# PIR_datalogger.net
KiCad netlist of a schematic drawn in EAGLE
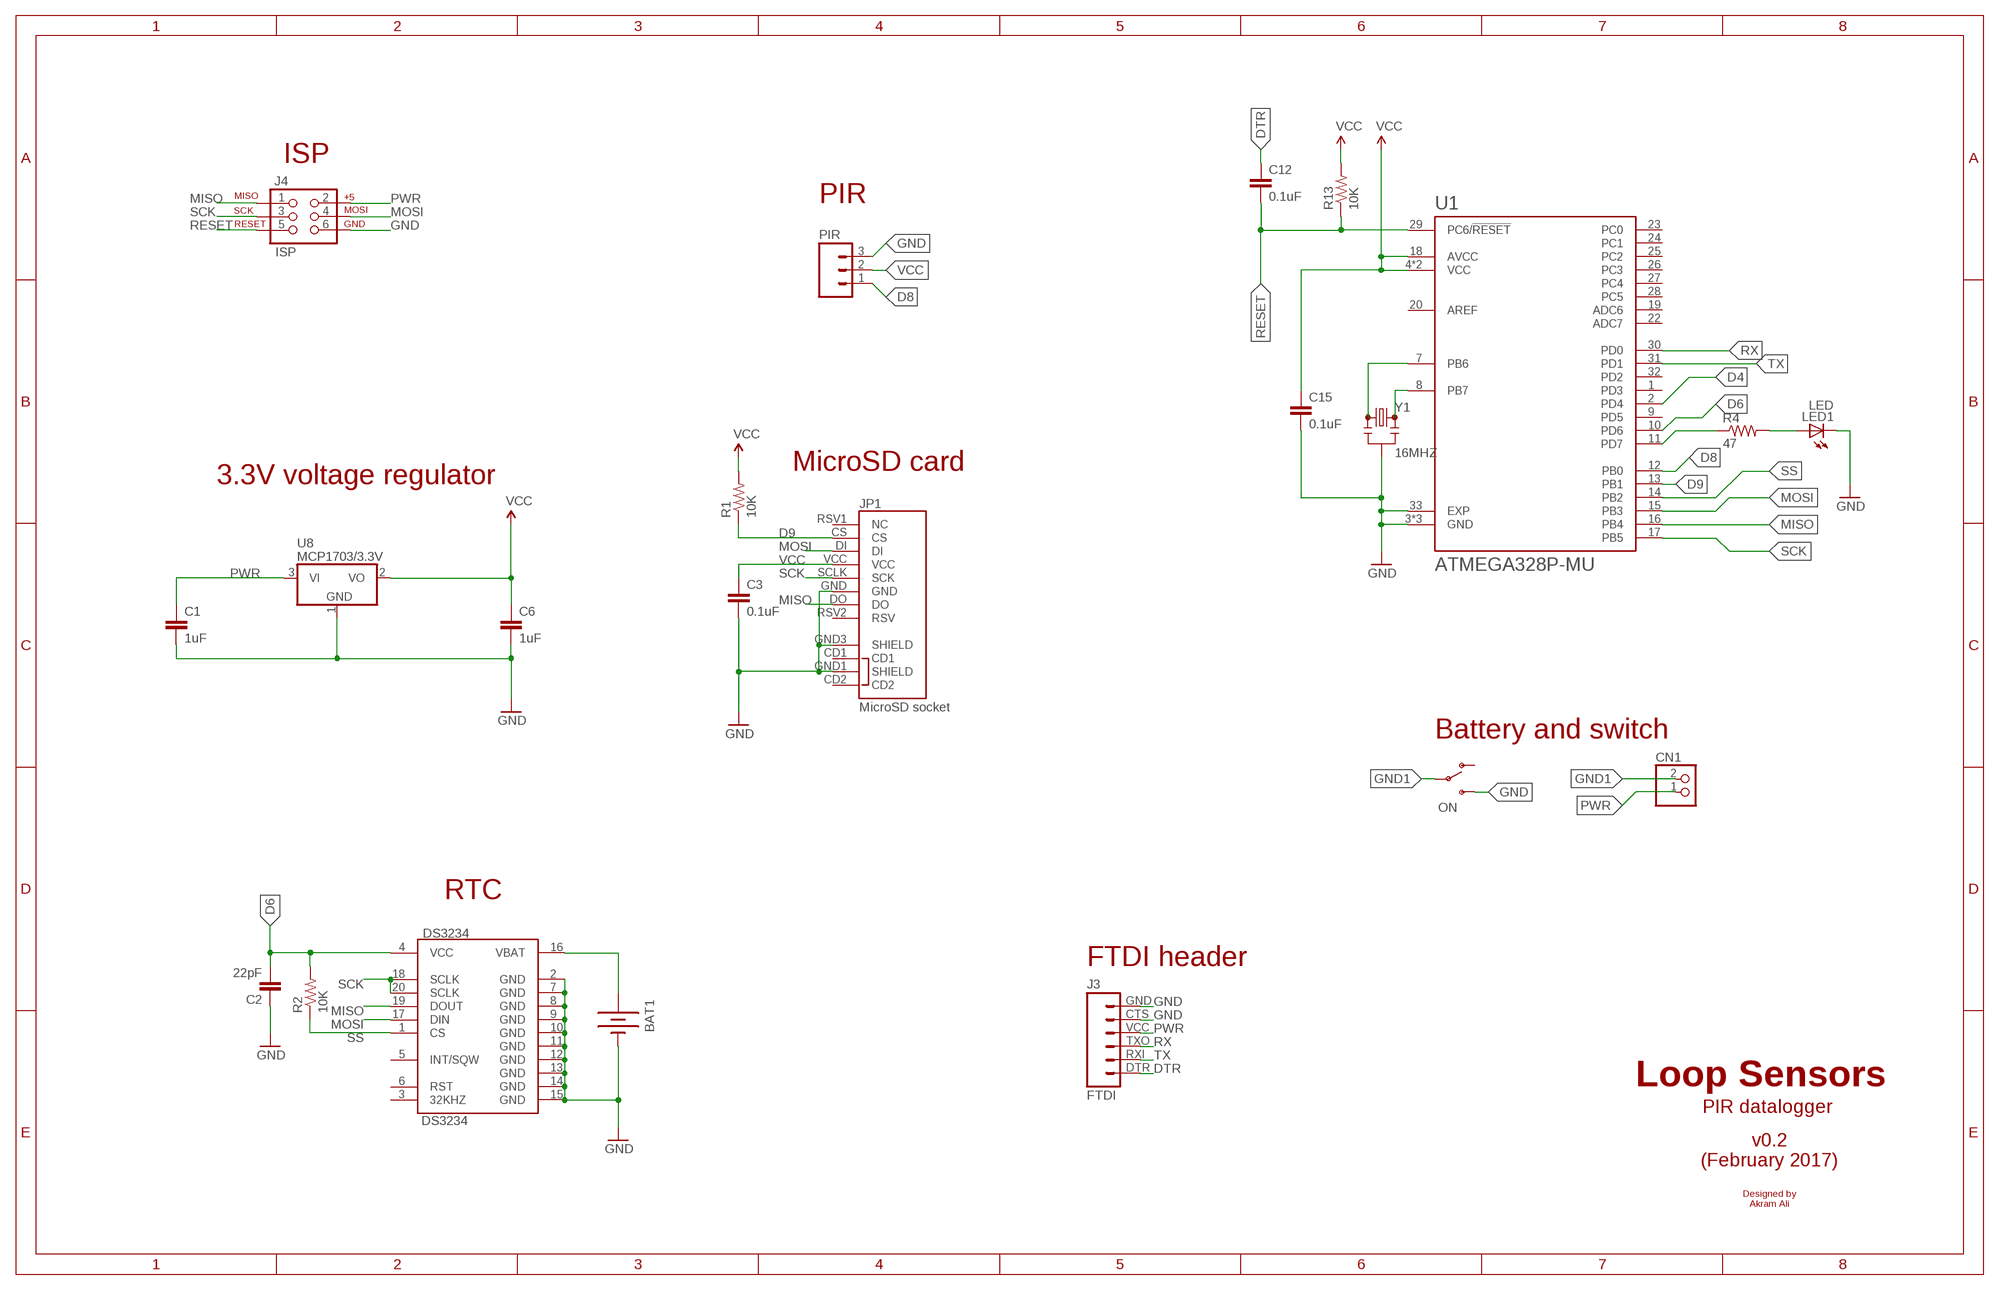
[diagram p0: schematic, sheet 1]

(export (version "E")
  (design (tool "Eeschema 10.0.6"))
  (components
    (comp (ref "BAT1")
      (value "BATTERY12MM")
      (footprint "eagle-import:BATTCON_12MM")
      (fields (field (name "MPN") "3000"))
      (libsource (lib "eagle-import") (part "BATTERY12MM"))
    )
    (comp (ref "C1")
      (value "1uF")
      (footprint "eagle-import:0805")
      (fields (field (name "MPN") "CC0805KKX7R7BB105"))
      (libsource (lib "eagle-import") (part "CAP0805"))
    )
    (comp (ref "C2")
      (value "22pF")
      (footprint "eagle-import:0805")
      (fields (field (name "MPN") "AC0805KRX7R9BB104"))
      (libsource (lib "eagle-import") (part "SparkFun-Passives_CAP0805"))
    )
    (comp (ref "C3")
      (value "0.1uF")
      (footprint "eagle-import:0805")
      (fields (field (name "MPN") "AC0805KRX7R9BB104"))
      (libsource (lib "eagle-import") (part "SparkFun-Passives_CAP0805"))
    )
    (comp (ref "C6")
      (value "1uF")
      (footprint "eagle-import:0805")
      (fields (field (name "MPN") "CC0805KKX7R7BB105"))
      (libsource (lib "eagle-import") (part "CAP0805"))
    )
    (comp (ref "C12")
      (value "0.1uF")
      (footprint "eagle-import:0805")
      (fields (field (name "MPN") "AC0805KRX7R9BB104"))
      (libsource (lib "eagle-import") (part "SparkFun-Passives_CAP0805"))
    )
    (comp (ref "C15")
      (value "0.1uF")
      (footprint "eagle-import:0805")
      (fields (field (name "MPN") "AC0805KRX7R9BB104"))
      (libsource (lib "eagle-import") (part "SparkFun-Passives_CAP0805"))
    )
    (comp (ref "CN1")
      (value "JST_2PIN-SMT-RA")
      (footprint "eagle-import:JST-PH-2-SMT-RA")
      (libsource (lib "eagle-import") (part "JST_2PIN-SMT-RA"))
    )
    (comp (ref "DS3234")
      (value "DS3234")
      (footprint "eagle-import:DS3234")
      (fields (field (name "MPN") "DS3234S#"))
      (libsource (lib "eagle-import") (part "DS3234"))
    )
    (comp (ref "J3")
      (value "FTDI")
      (footprint "eagle-import:FTDI_BASIC")
      (libsource (lib "eagle-import") (part "FTDI_BASICPTH"))
    )
    (comp (ref "J4")
      (value "ISP")
      (footprint "eagle-import:2X3")
      (libsource (lib "eagle-import") (part "AVR_SPI_PRG_6PTH"))
    )
    (comp (ref "JP1")
      (value "MicroSD socket")
      (footprint "eagle-import:MICRO-SD-SOCKET-PP")
      (libsource (lib "eagle-import") (part "USD-SOCKETNEW"))
    )
    (comp (ref "LED1")
      (value "LED")
      (footprint "eagle-import:CHIPLED_0805")
      (fields (field (name "MPN") "150080BS75000"))
      (libsource (lib "eagle-import") (part "LEDCHIPLED_0805"))
    )
    (comp (ref "ON")
      (value "SWITCH-SPDT-SMD-A")
      (footprint "eagle-import:SWITCH-SPST-SMD-A")
      (libsource (lib "eagle-import") (part "SWITCH-SPDT-SMD-A"))
    )
    (comp (ref "PIR")
      (value "M03PTH")
      (footprint "eagle-import:1X03")
      (libsource (lib "eagle-import") (part "M03PTH"))
    )
    (comp (ref "R1")
      (value "10K")
      (footprint "eagle-import:0805")
      (fields (field (name "MPN") "RC0805JR-0710KL"))
      (libsource (lib "eagle-import") (part "RESISTOR0805-RES"))
    )
    (comp (ref "R2")
      (value "10K")
      (footprint "eagle-import:0805")
      (fields (field (name "MPN") "RC0805JR-0710KL"))
      (libsource (lib "eagle-import") (part "RESISTOR0805-RES"))
    )
    (comp (ref "R4")
      (value "47")
      (footprint "eagle-import:0805")
      (fields (field (name "MPN") "RC0805JR-0747RL"))
      (libsource (lib "eagle-import") (part "SparkFun-Resistors_RESISTOR0805-RES"))
    )
    (comp (ref "R13")
      (value "10K")
      (footprint "eagle-import:0805")
      (fields (field (name "MPN") "RC0805JR-0710KL"))
      (libsource (lib "eagle-import") (part "RESISTOR0805-RES"))
    )
    (comp (ref "U1")
      (value "ATMEGA328P-MU")
      (footprint "eagle-import:QFN50P500X500X100-33N")
      (fields (field (name "MF") "Atmel"))
      (libsource (lib "eagle-import") (part "ATMEGA328P-MU"))
    )
    (comp (ref "U8")
      (value "MCP1703/3.3V")
      (footprint "eagle-import:SOT23")
      (fields (field (name "MPN") "MCP1703T-2502E/CB"))
      (libsource (lib "eagle-import") (part "MCP1703CB"))
    )
    (comp (ref "Y1")
      (value "16MHZ")
      (footprint "eagle-import:RESONATOR-SMD")
      (fields (field (name "MPN") "CSTCE16M0V53-R0"))
      (libsource (lib "eagle-import") (part "RESONATOR16MHZ"))
    )
  )
  (nets
    (net (code "1") (name "D4") (class "Default")
      (node (ref "U1") (pin "2") (pinfunction "PD4_2") (pintype "bidirectional"))
    )
    (net (code "2") (name "D6") (class "Default")
      (node (ref "C2") (pin "2") (pinfunction "2_2") (pintype "passive"))
      (node (ref "DS3234") (pin "4") (pinfunction "VCC_4") (pintype "bidirectional"))
      (node (ref "R2") (pin "2") (pinfunction "2_2") (pintype "passive"))
      (node (ref "U1") (pin "10") (pinfunction "PD6_10") (pintype "bidirectional"))
    )
    (net (code "3") (name "D8") (class "Default")
      (node (ref "PIR") (pin "1") (pinfunction "1_1") (pintype "passive"))
      (node (ref "U1") (pin "12") (pinfunction "PB0_12") (pintype "bidirectional"))
    )
    (net (code "4") (name "D9") (class "Default")
      (node (ref "JP1") (pin "CS") (pinfunction "CS_CS") (pintype "bidirectional"))
      (node (ref "R1") (pin "1") (pinfunction "1_1") (pintype "passive"))
      (node (ref "U1") (pin "13") (pinfunction "PB1_13") (pintype "bidirectional"))
    )
    (net (code "5") (name "DTR") (class "Default")
      (node (ref "C12") (pin "1") (pinfunction "1_1") (pintype "passive"))
      (node (ref "J3") (pin "DTR") (pinfunction "1_DTR") (pintype "passive"))
    )
    (net (code "6") (name "GND") (class "Default")
      (node (ref "BAT1") (pin "GND") (pinfunction "-_GND") (pintype "power_in"))
      (node (ref "C1") (pin "2") (pinfunction "2_2") (pintype "passive"))
      (node (ref "C15") (pin "2") (pinfunction "2_2") (pintype "passive"))
      (node (ref "C2") (pin "1") (pinfunction "1_1") (pintype "passive"))
      (node (ref "C3") (pin "2") (pinfunction "2_2") (pintype "passive"))
      (node (ref "C6") (pin "2") (pinfunction "2_2") (pintype "passive"))
      (node (ref "DS3234") (pin "10") (pinfunction "GND_10") (pintype "bidirectional"))
      (node (ref "DS3234") (pin "11") (pinfunction "GND_11") (pintype "bidirectional"))
      (node (ref "DS3234") (pin "12") (pinfunction "GND_12") (pintype "bidirectional"))
      (node (ref "DS3234") (pin "13") (pinfunction "GND_13") (pintype "bidirectional"))
      (node (ref "DS3234") (pin "14") (pinfunction "GND_14") (pintype "bidirectional"))
      (node (ref "DS3234") (pin "15") (pinfunction "GND_15") (pintype "bidirectional"))
      (node (ref "DS3234") (pin "2") (pinfunction "GND_2") (pintype "bidirectional"))
      (node (ref "DS3234") (pin "7") (pinfunction "GND_7") (pintype "bidirectional"))
      (node (ref "DS3234") (pin "8") (pinfunction "GND_8") (pintype "bidirectional"))
      (node (ref "DS3234") (pin "9") (pinfunction "GND_9") (pintype "bidirectional"))
      (node (ref "J3") (pin "CTS") (pinfunction "5_CTS") (pintype "passive"))
      (node (ref "J3") (pin "GND") (pinfunction "6_GND") (pintype "passive"))
      (node (ref "J4") (pin "6") (pinfunction "6_6") (pintype "passive"))
      (node (ref "JP1") (pin "GND") (pinfunction "GND_GND") (pintype "bidirectional"))
      (node (ref "JP1") (pin "GND1") (pinfunction "SHIELD_GND1") (pintype "bidirectional"))
      (node (ref "JP1") (pin "GND3") (pinfunction "SHIELD_GND3") (pintype "bidirectional"))
      (node (ref "LED1") (pin "C") (pinfunction "C_C") (pintype "passive"))
      (node (ref "ON") (pin "3") (pinfunction "S_3") (pintype "passive"))
      (node (ref "PIR") (pin "3") (pinfunction "3_3") (pintype "passive"))
      (node (ref "U1") (pin "21") (pinfunction "GND_21") (pintype "power_in"))
      (node (ref "U1") (pin "3") (pinfunction "GND_3") (pintype "power_in"))
      (node (ref "U1") (pin "33") (pinfunction "EXP_33") (pintype "power_in"))
      (node (ref "U1") (pin "5") (pinfunction "GND_5") (pintype "power_in"))
      (node (ref "U8") (pin "1") (pinfunction "GND_1") (pintype "passive"))
      (node (ref "Y1") (pin "2") (pinfunction "2_2") (pintype "passive"))
    )
    (net (code "7") (name "GND1") (class "Default")
      (node (ref "CN1") (pin "2") (pinfunction "1_2") (pintype "passive"))
      (node (ref "ON") (pin "2") (pinfunction "P_2") (pintype "passive"))
    )
    (net (code "8") (name "MISO") (class "Default")
      (node (ref "DS3234") (pin "19") (pinfunction "DOUT_19") (pintype "bidirectional"))
      (node (ref "J4") (pin "1") (pinfunction "1_1") (pintype "passive"))
      (node (ref "JP1") (pin "DO") (pinfunction "DO_DO") (pintype "bidirectional"))
      (node (ref "U1") (pin "16") (pinfunction "PB4_16") (pintype "bidirectional"))
    )
    (net (code "9") (name "MOSI") (class "Default")
      (node (ref "DS3234") (pin "17") (pinfunction "DIN_17") (pintype "bidirectional"))
      (node (ref "J4") (pin "4") (pinfunction "4_4") (pintype "passive"))
      (node (ref "JP1") (pin "DI") (pinfunction "DI_DI") (pintype "bidirectional"))
      (node (ref "U1") (pin "15") (pinfunction "PB3_15") (pintype "bidirectional"))
    )
    (net (code "10") (name "Net-(BAT1-+)") (class "Default")
      (node (ref "BAT1") (pin "PWR@1") (pinfunction "+_PWR@1") (pintype "power_in"))
      (node (ref "DS3234") (pin "16") (pinfunction "VBAT_16") (pintype "bidirectional"))
    )
    (net (code "11") (name "Net-(LED1-PadA)") (class "Default")
      (node (ref "LED1") (pin "A") (pinfunction "A_A") (pintype "passive"))
      (node (ref "R4") (pin "2") (pinfunction "2_2") (pintype "passive"))
    )
    (net (code "12") (name "Net-(U1-PB6)") (class "Default")
      (node (ref "U1") (pin "7") (pinfunction "PB6_7") (pintype "bidirectional"))
      (node (ref "Y1") (pin "1") (pinfunction "1_1") (pintype "passive"))
    )
    (net (code "13") (name "Net-(U1-PB7)") (class "Default")
      (node (ref "U1") (pin "8") (pinfunction "PB7_8") (pintype "bidirectional"))
      (node (ref "Y1") (pin "3") (pinfunction "3_3") (pintype "passive"))
    )
    (net (code "14") (name "Net-(U1-PD7)") (class "Default")
      (node (ref "R4") (pin "1") (pinfunction "1_1") (pintype "passive"))
      (node (ref "U1") (pin "11") (pinfunction "PD7_11") (pintype "bidirectional"))
    )
    (net (code "15") (name "PWR") (class "Default")
      (node (ref "C1") (pin "1") (pinfunction "1_1") (pintype "passive"))
      (node (ref "CN1") (pin "1") (pinfunction "2_1") (pintype "passive"))
      (node (ref "J3") (pin "VCC") (pinfunction "4_VCC") (pintype "passive"))
      (node (ref "J4") (pin "2") (pinfunction "2_2") (pintype "passive"))
      (node (ref "U8") (pin "3") (pinfunction "VI_3") (pintype "input"))
    )
    (net (code "16") (name "RESET") (class "Default")
      (node (ref "C12") (pin "2") (pinfunction "2_2") (pintype "passive"))
      (node (ref "J4") (pin "5") (pinfunction "5_5") (pintype "passive"))
      (node (ref "R13") (pin "1") (pinfunction "1_1") (pintype "passive"))
      (node (ref "U1") (pin "29") (pinfunction "PC6/~{RESET}_29") (pintype "bidirectional"))
    )
    (net (code "17") (name "RX") (class "Default")
      (node (ref "J3") (pin "TXO") (pinfunction "3_TXO") (pintype "passive"))
      (node (ref "U1") (pin "30") (pinfunction "PD0_30") (pintype "bidirectional"))
    )
    (net (code "18") (name "SCK") (class "Default")
      (node (ref "DS3234") (pin "18") (pinfunction "SCLK_18") (pintype "bidirectional"))
      (node (ref "DS3234") (pin "20") (pinfunction "SCLK_20") (pintype "bidirectional"))
      (node (ref "J4") (pin "3") (pinfunction "3_3") (pintype "passive"))
      (node (ref "JP1") (pin "SCLK") (pinfunction "SCK_SCLK") (pintype "bidirectional"))
      (node (ref "U1") (pin "17") (pinfunction "PB5_17") (pintype "bidirectional"))
    )
    (net (code "19") (name "SS") (class "Default")
      (node (ref "DS3234") (pin "1") (pinfunction "CS_1") (pintype "bidirectional"))
      (node (ref "R2") (pin "1") (pinfunction "1_1") (pintype "passive"))
      (node (ref "U1") (pin "14") (pinfunction "PB2_14") (pintype "bidirectional"))
    )
    (net (code "20") (name "TX") (class "Default")
      (node (ref "J3") (pin "RXI") (pinfunction "2_RXI") (pintype "passive"))
      (node (ref "U1") (pin "31") (pinfunction "PD1_31") (pintype "bidirectional"))
    )
    (net (code "21") (name "VCC") (class "Default")
      (node (ref "C15") (pin "1") (pinfunction "1_1") (pintype "passive"))
      (node (ref "C3") (pin "1") (pinfunction "1_1") (pintype "passive"))
      (node (ref "C6") (pin "1") (pinfunction "1_1") (pintype "passive"))
      (node (ref "JP1") (pin "VCC") (pinfunction "VCC_VCC") (pintype "bidirectional"))
      (node (ref "PIR") (pin "2") (pinfunction "2_2") (pintype "passive"))
      (node (ref "R1") (pin "2") (pinfunction "2_2") (pintype "passive"))
      (node (ref "R13") (pin "2") (pinfunction "2_2") (pintype "passive"))
      (node (ref "U1") (pin "18") (pinfunction "AVCC_18") (pintype "power_in"))
      (node (ref "U1") (pin "4") (pinfunction "VCC_4") (pintype "power_in"))
      (node (ref "U1") (pin "6") (pinfunction "VCC_6") (pintype "power_in"))
      (node (ref "U8") (pin "2") (pinfunction "VO_2") (pintype "passive"))
    )
    (net (code "22") (name "unconnected-(DS3234-32KHZ-Pad3)") (class "Default")
      (node (ref "DS3234") (pin "3") (pinfunction "32KHZ_3") (pintype "bidirectional"))
    )
    (net (code "23") (name "unconnected-(DS3234-INT{slash}SQW-Pad5)") (class "Default")
      (node (ref "DS3234") (pin "5") (pinfunction "INT/SQW_5") (pintype "bidirectional"))
    )
    (net (code "24") (name "unconnected-(DS3234-RST-Pad6)") (class "Default")
      (node (ref "DS3234") (pin "6") (pinfunction "RST_6") (pintype "bidirectional"))
    )
    (net (code "25") (name "unconnected-(JP1-NC-PadRSV1)") (class "Default")
      (node (ref "JP1") (pin "RSV1") (pinfunction "NC_RSV1") (pintype "bidirectional"))
    )
    (net (code "26") (name "unconnected-(JP1-PadCD1)") (class "Default")
      (node (ref "JP1") (pin "CD1") (pinfunction "CD1_CD1") (pintype "bidirectional"))
    )
    (net (code "27") (name "unconnected-(JP1-PadCD2)") (class "Default")
      (node (ref "JP1") (pin "CD2") (pinfunction "CD2_CD2") (pintype "bidirectional"))
    )
    (net (code "28") (name "unconnected-(JP1-RSV-PadRSV2)") (class "Default")
      (node (ref "JP1") (pin "RSV2") (pinfunction "RSV_RSV2") (pintype "bidirectional"))
    )
    (net (code "29") (name "unconnected-(ON-O-Pad1)") (class "Default")
      (node (ref "ON") (pin "1") (pinfunction "O_1") (pintype "passive"))
    )
    (net (code "30") (name "unconnected-(U1-ADC6-Pad19)") (class "Default")
      (node (ref "U1") (pin "19") (pinfunction "ADC6_19") (pintype "bidirectional"))
    )
    (net (code "31") (name "unconnected-(U1-ADC7-Pad22)") (class "Default")
      (node (ref "U1") (pin "22") (pinfunction "ADC7_22") (pintype "bidirectional"))
    )
    (net (code "32") (name "unconnected-(U1-AREF-Pad20)") (class "Default")
      (node (ref "U1") (pin "20") (pinfunction "AREF_20") (pintype "input"))
    )
    (net (code "33") (name "unconnected-(U1-PC0-Pad23)") (class "Default")
      (node (ref "U1") (pin "23") (pinfunction "PC0_23") (pintype "bidirectional"))
    )
    (net (code "34") (name "unconnected-(U1-PC1-Pad24)") (class "Default")
      (node (ref "U1") (pin "24") (pinfunction "PC1_24") (pintype "bidirectional"))
    )
    (net (code "35") (name "unconnected-(U1-PC2-Pad25)") (class "Default")
      (node (ref "U1") (pin "25") (pinfunction "PC2_25") (pintype "bidirectional"))
    )
    (net (code "36") (name "unconnected-(U1-PC3-Pad26)") (class "Default")
      (node (ref "U1") (pin "26") (pinfunction "PC3_26") (pintype "bidirectional"))
    )
    (net (code "37") (name "unconnected-(U1-PC4-Pad27)") (class "Default")
      (node (ref "U1") (pin "27") (pinfunction "PC4_27") (pintype "bidirectional"))
    )
    (net (code "38") (name "unconnected-(U1-PC5-Pad28)") (class "Default")
      (node (ref "U1") (pin "28") (pinfunction "PC5_28") (pintype "bidirectional"))
    )
    (net (code "39") (name "unconnected-(U1-PD2-Pad32)") (class "Default")
      (node (ref "U1") (pin "32") (pinfunction "PD2_32") (pintype "bidirectional"))
    )
    (net (code "40") (name "unconnected-(U1-PD3-Pad1)") (class "Default")
      (node (ref "U1") (pin "1") (pinfunction "PD3_1") (pintype "bidirectional"))
    )
    (net (code "41") (name "unconnected-(U1-PD5-Pad9)") (class "Default")
      (node (ref "U1") (pin "9") (pinfunction "PD5_9") (pintype "bidirectional"))
    )
  )
)
